# 05_Mechanical.net
KiCad netlist of a schematic drawn in Altium Designer
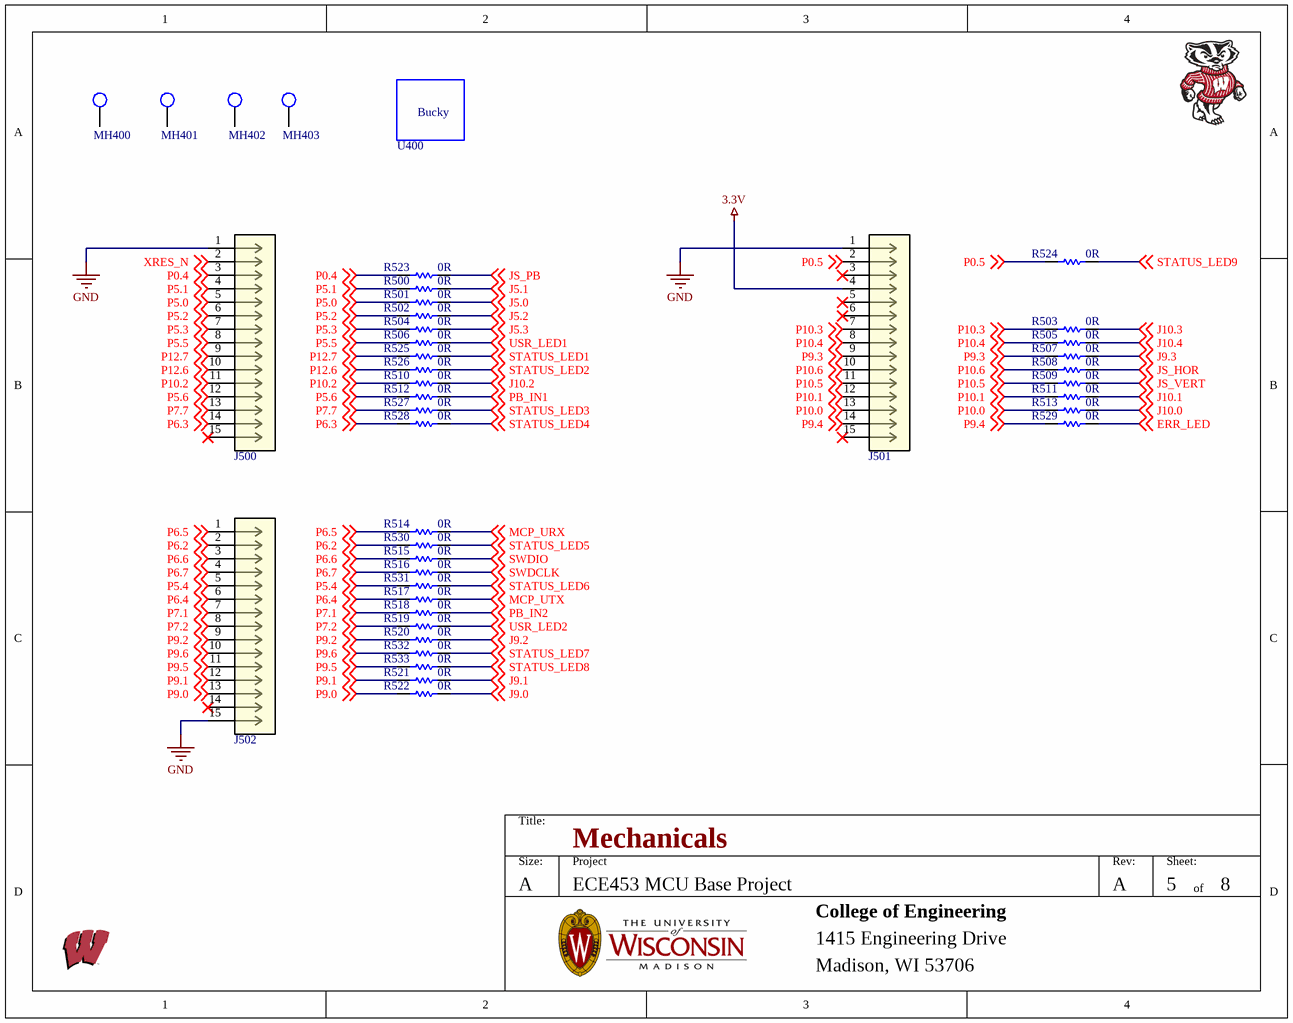
[diagram p0: 05_Mechanical.SchDoc]

(export (version "E")
  (design (tool "Eeschema 10.0.6"))
  (components
    (comp (ref "J500")
      (value "68000-115HLF")
      (footprint "CONN_15POS_2P54MM")
      (description "Conn Unshrouded Header HDR 15 POS 2.54mm Solder ST Thru-Hole")
      (fields
        (field (name "MANUFACTURER") "Adam Equipment")
        (field (name "MANUFACTURER PART NUMBER") "PH1-15-UA")
        (field (name "COPYRIGHT") "Copyright (C) 2024 Ultra Librarian. All rights reserved.")
      )
      (libsource (lib "ECE453_S24") (part "CONN_HEADER_POS_30_2.54MM"))
    )
    (comp (ref "J501")
      (value "68000-115HLF")
      (footprint "CONN_15POS_2P54MM")
      (description "Conn Unshrouded Header HDR 15 POS 2.54mm Solder ST Thru-Hole")
      (fields
        (field (name "MANUFACTURER") "Adam Equipment")
        (field (name "MANUFACTURER PART NUMBER") "PH1-15-UA")
        (field (name "COPYRIGHT") "Copyright (C) 2024 Ultra Librarian. All rights reserved.")
      )
      (libsource (lib "ECE453_S24") (part "CONN_HEADER_POS_30_2.54MM"))
    )
    (comp (ref "J502")
      (value "68000-115HLF")
      (footprint "CONN_15POS_2P54MM")
      (description "Conn Unshrouded Header HDR 15 POS 2.54mm Solder ST Thru-Hole")
      (fields
        (field (name "MANUFACTURER") "Adam Equipment")
        (field (name "MANUFACTURER PART NUMBER") "PH1-15-UA")
        (field (name "COPYRIGHT") "Copyright (C) 2024 Ultra Librarian. All rights reserved.")
      )
      (libsource (lib "ECE453_S24") (part "CONN_HEADER_POS_30_2.54MM"))
    )
    (comp (ref "MH400")
      (value "MHOLE_2_55MM")
      (footprint "MHOLE_2_55MM")
      (description "Mounting Holde")
      (fields (field (name "MANUFACTURER PART NUMBER") "UW MTHOLE"))
      (libsource (lib "ECE453_S24") (part "MHOLE_2_55MM"))
    )
    (comp (ref "MH401")
      (value "MHOLE_2_55MM")
      (footprint "MHOLE_2_55MM")
      (description "Mounting Holde")
      (fields (field (name "MANUFACTURER PART NUMBER") "UW MTHOLE"))
      (libsource (lib "ECE453_S24") (part "MHOLE_2_55MM"))
    )
    (comp (ref "MH402")
      (value "MHOLE_2_55MM")
      (footprint "MHOLE_2_55MM")
      (description "Mounting Holde")
      (fields (field (name "MANUFACTURER PART NUMBER") "UW MTHOLE"))
      (libsource (lib "ECE453_S24") (part "MHOLE_2_55MM"))
    )
    (comp (ref "MH403")
      (value "MHOLE_2_55MM")
      (footprint "MHOLE_2_55MM")
      (description "Mounting Holde")
      (fields (field (name "MANUFACTURER PART NUMBER") "UW MTHOLE"))
      (libsource (lib "ECE453_S24") (part "MHOLE_2_55MM"))
    )
    (comp (ref "R500")
      (value "0R")
      (footprint "RESC2013X70X40NL20T20")
      (description "Chip Resistor, 0 Ohm, +/- 1%, 0.125 W, -55 to 155 degC, 0805 (2012 Metric), RoHS, Tape and Reel")
      (fields (field (name "PARTNUMBER") "ERJ-6GEY0R00V") (field (name "TOLERANCE") "5%"))
      (libsource (lib "Altium Content Vault") (part "RES-2"))
    )
    (comp (ref "R501")
      (value "0R")
      (footprint "RESC2013X70X40NL20T20")
      (description "Chip Resistor, 0 Ohm, +/- 1%, 0.125 W, -55 to 155 degC, 0805 (2012 Metric), RoHS, Tape and Reel")
      (fields (field (name "PARTNUMBER") "ERJ-6GEY0R00V") (field (name "TOLERANCE") "5%"))
      (libsource (lib "Altium Content Vault") (part "RES-2"))
    )
    (comp (ref "R502")
      (value "0R")
      (footprint "RESC2013X70X40NL20T20")
      (description "Chip Resistor, 0 Ohm, +/- 1%, 0.125 W, -55 to 155 degC, 0805 (2012 Metric), RoHS, Tape and Reel")
      (fields (field (name "PARTNUMBER") "ERJ-6GEY0R00V") (field (name "TOLERANCE") "5%"))
      (libsource (lib "Altium Content Vault") (part "RES-2"))
    )
    (comp (ref "R503")
      (value "0R")
      (footprint "RESC2013X70X40NL20T20")
      (description "Chip Resistor, 0 Ohm, +/- 1%, 0.125 W, -55 to 155 degC, 0805 (2012 Metric), RoHS, Tape and Reel")
      (fields (field (name "PARTNUMBER") "ERJ-6GEY0R00V") (field (name "TOLERANCE") "5%"))
      (libsource (lib "Altium Content Vault") (part "RES-2"))
    )
    (comp (ref "R504")
      (value "0R")
      (footprint "RESC2013X70X40NL20T20")
      (description "Chip Resistor, 0 Ohm, +/- 1%, 0.125 W, -55 to 155 degC, 0805 (2012 Metric), RoHS, Tape and Reel")
      (fields (field (name "PARTNUMBER") "ERJ-6GEY0R00V") (field (name "TOLERANCE") "5%"))
      (libsource (lib "Altium Content Vault") (part "RES-2"))
    )
    (comp (ref "R505")
      (value "0R")
      (footprint "RESC2013X70X40NL20T20")
      (description "Chip Resistor, 0 Ohm, +/- 1%, 0.125 W, -55 to 155 degC, 0805 (2012 Metric), RoHS, Tape and Reel")
      (fields (field (name "PARTNUMBER") "ERJ-6GEY0R00V") (field (name "TOLERANCE") "5%"))
      (libsource (lib "Altium Content Vault") (part "RES-2"))
    )
    (comp (ref "R506")
      (value "0R")
      (footprint "RESC2013X70X40NL20T20")
      (description "Chip Resistor, 0 Ohm, +/- 1%, 0.125 W, -55 to 155 degC, 0805 (2012 Metric), RoHS, Tape and Reel")
      (fields (field (name "PARTNUMBER") "ERJ-6GEY0R00V") (field (name "TOLERANCE") "5%"))
      (libsource (lib "Altium Content Vault") (part "RES-2"))
    )
    (comp (ref "R507")
      (value "0R")
      (footprint "RESC2013X70X40NL20T20")
      (description "Chip Resistor, 0 Ohm, +/- 1%, 0.125 W, -55 to 155 degC, 0805 (2012 Metric), RoHS, Tape and Reel")
      (fields (field (name "PARTNUMBER") "ERJ-6GEY0R00V") (field (name "TOLERANCE") "5%"))
      (libsource (lib "Altium Content Vault") (part "RES-2"))
    )
    (comp (ref "R508")
      (value "0R")
      (footprint "RESC2013X70X40NL20T20")
      (description "Chip Resistor, 0 Ohm, +/- 1%, 0.125 W, -55 to 155 degC, 0805 (2012 Metric), RoHS, Tape and Reel")
      (fields (field (name "PARTNUMBER") "ERJ-6GEY0R00V") (field (name "TOLERANCE") "5%"))
      (libsource (lib "Altium Content Vault") (part "RES-2"))
    )
    (comp (ref "R509")
      (value "0R")
      (footprint "RESC2013X70X40NL20T20")
      (description "Chip Resistor, 0 Ohm, +/- 1%, 0.125 W, -55 to 155 degC, 0805 (2012 Metric), RoHS, Tape and Reel")
      (fields (field (name "PARTNUMBER") "ERJ-6GEY0R00V") (field (name "TOLERANCE") "5%"))
      (libsource (lib "Altium Content Vault") (part "RES-2"))
    )
    (comp (ref "R510")
      (value "0R")
      (footprint "RESC2013X70X40NL20T20")
      (description "Chip Resistor, 0 Ohm, +/- 1%, 0.125 W, -55 to 155 degC, 0805 (2012 Metric), RoHS, Tape and Reel")
      (fields (field (name "PARTNUMBER") "ERJ-6GEY0R00V") (field (name "TOLERANCE") "5%"))
      (libsource (lib "Altium Content Vault") (part "RES-2"))
    )
    (comp (ref "R511")
      (value "0R")
      (footprint "RESC2013X70X40NL20T20")
      (description "Chip Resistor, 0 Ohm, +/- 1%, 0.125 W, -55 to 155 degC, 0805 (2012 Metric), RoHS, Tape and Reel")
      (fields (field (name "PARTNUMBER") "ERJ-6GEY0R00V") (field (name "TOLERANCE") "5%"))
      (libsource (lib "Altium Content Vault") (part "RES-2"))
    )
    (comp (ref "R512")
      (value "0R")
      (footprint "RESC2013X70X40NL20T20")
      (description "Chip Resistor, 0 Ohm, +/- 1%, 0.125 W, -55 to 155 degC, 0805 (2012 Metric), RoHS, Tape and Reel")
      (fields (field (name "PARTNUMBER") "ERJ-6GEY0R00V") (field (name "TOLERANCE") "5%"))
      (libsource (lib "Altium Content Vault") (part "RES-2"))
    )
    (comp (ref "R513")
      (value "0R")
      (footprint "RESC2013X70X40NL20T20")
      (description "Chip Resistor, 0 Ohm, +/- 1%, 0.125 W, -55 to 155 degC, 0805 (2012 Metric), RoHS, Tape and Reel")
      (fields (field (name "PARTNUMBER") "ERJ-6GEY0R00V") (field (name "TOLERANCE") "5%"))
      (libsource (lib "Altium Content Vault") (part "RES-2"))
    )
    (comp (ref "R514")
      (value "0R")
      (footprint "RESC2013X70X40NL20T20")
      (description "Chip Resistor, 0 Ohm, +/- 1%, 0.125 W, -55 to 155 degC, 0805 (2012 Metric), RoHS, Tape and Reel")
      (fields (field (name "PARTNUMBER") "ERJ-6GEY0R00V") (field (name "TOLERANCE") "5%"))
      (libsource (lib "Altium Content Vault") (part "RES-2"))
    )
    (comp (ref "R515")
      (value "0R")
      (footprint "RESC2013X70X40NL20T20")
      (description "Chip Resistor, 0 Ohm, +/- 1%, 0.125 W, -55 to 155 degC, 0805 (2012 Metric), RoHS, Tape and Reel")
      (fields (field (name "PARTNUMBER") "ERJ-6GEY0R00V") (field (name "TOLERANCE") "5%"))
      (libsource (lib "Altium Content Vault") (part "RES-2"))
    )
    (comp (ref "R516")
      (value "0R")
      (footprint "RESC2013X70X40NL20T20")
      (description "Chip Resistor, 0 Ohm, +/- 1%, 0.125 W, -55 to 155 degC, 0805 (2012 Metric), RoHS, Tape and Reel")
      (fields (field (name "PARTNUMBER") "ERJ-6GEY0R00V") (field (name "TOLERANCE") "5%"))
      (libsource (lib "Altium Content Vault") (part "RES-2"))
    )
    (comp (ref "R517")
      (value "0R")
      (footprint "RESC2013X70X40NL20T20")
      (description "Chip Resistor, 0 Ohm, +/- 1%, 0.125 W, -55 to 155 degC, 0805 (2012 Metric), RoHS, Tape and Reel")
      (fields (field (name "PARTNUMBER") "ERJ-6GEY0R00V") (field (name "TOLERANCE") "5%"))
      (libsource (lib "Altium Content Vault") (part "RES-2"))
    )
    (comp (ref "R518")
      (value "0R")
      (footprint "RESC2013X70X40NL20T20")
      (description "Chip Resistor, 0 Ohm, +/- 1%, 0.125 W, -55 to 155 degC, 0805 (2012 Metric), RoHS, Tape and Reel")
      (fields (field (name "PARTNUMBER") "ERJ-6GEY0R00V") (field (name "TOLERANCE") "5%"))
      (libsource (lib "Altium Content Vault") (part "RES-2"))
    )
    (comp (ref "R519")
      (value "0R")
      (footprint "RESC2013X70X40NL20T20")
      (description "Chip Resistor, 0 Ohm, +/- 1%, 0.125 W, -55 to 155 degC, 0805 (2012 Metric), RoHS, Tape and Reel")
      (fields (field (name "PARTNUMBER") "ERJ-6GEY0R00V") (field (name "TOLERANCE") "5%"))
      (libsource (lib "Altium Content Vault") (part "RES-2"))
    )
    (comp (ref "R520")
      (value "0R")
      (footprint "RESC2013X70X40NL20T20")
      (description "Chip Resistor, 0 Ohm, +/- 1%, 0.125 W, -55 to 155 degC, 0805 (2012 Metric), RoHS, Tape and Reel")
      (fields (field (name "PARTNUMBER") "ERJ-6GEY0R00V") (field (name "TOLERANCE") "5%"))
      (libsource (lib "Altium Content Vault") (part "RES-2"))
    )
    (comp (ref "R521")
      (value "0R")
      (footprint "RESC2013X70X40NL20T20")
      (description "Chip Resistor, 0 Ohm, +/- 1%, 0.125 W, -55 to 155 degC, 0805 (2012 Metric), RoHS, Tape and Reel")
      (fields (field (name "PARTNUMBER") "ERJ-6GEY0R00V") (field (name "TOLERANCE") "5%"))
      (libsource (lib "Altium Content Vault") (part "RES-2"))
    )
    (comp (ref "R522")
      (value "0R")
      (footprint "RESC2013X70X40NL20T20")
      (description "Chip Resistor, 0 Ohm, +/- 1%, 0.125 W, -55 to 155 degC, 0805 (2012 Metric), RoHS, Tape and Reel")
      (fields (field (name "PARTNUMBER") "ERJ-6GEY0R00V") (field (name "TOLERANCE") "5%"))
      (libsource (lib "Altium Content Vault") (part "RES-2"))
    )
    (comp (ref "R523")
      (value "0R")
      (footprint "RESC2013X70X40NL20T20")
      (description "Chip Resistor, 0 Ohm, +/- 1%, 0.125 W, -55 to 155 degC, 0805 (2012 Metric), RoHS, Tape and Reel")
      (fields (field (name "PARTNUMBER") "ERJ-6GEY0R00V") (field (name "TOLERANCE") "5%"))
      (libsource (lib "Altium Content Vault") (part "RES-2"))
    )
    (comp (ref "R524")
      (value "0R")
      (footprint "RESC2013X70X40NL20T20")
      (description "Chip Resistor, 0 Ohm, +/- 1%, 0.125 W, -55 to 155 degC, 0805 (2012 Metric), RoHS, Tape and Reel")
      (fields (field (name "PARTNUMBER") "ERJ-6GEY0R00V") (field (name "TOLERANCE") "5%"))
      (libsource (lib "Altium Content Vault") (part "RES-2"))
    )
    (comp (ref "R525")
      (value "0R")
      (footprint "RESC2013X70X40NL20T20")
      (description "Chip Resistor, 0 Ohm, +/- 1%, 0.125 W, -55 to 155 degC, 0805 (2012 Metric), RoHS, Tape and Reel")
      (fields (field (name "PARTNUMBER") "ERJ-6GEY0R00V") (field (name "TOLERANCE") "5%"))
      (libsource (lib "Altium Content Vault") (part "RES-2"))
    )
    (comp (ref "R526")
      (value "0R")
      (footprint "RESC2013X70X40NL20T20")
      (description "Chip Resistor, 0 Ohm, +/- 1%, 0.125 W, -55 to 155 degC, 0805 (2012 Metric), RoHS, Tape and Reel")
      (fields (field (name "PARTNUMBER") "ERJ-6GEY0R00V") (field (name "TOLERANCE") "5%"))
      (libsource (lib "Altium Content Vault") (part "RES-2"))
    )
    (comp (ref "R527")
      (value "0R")
      (footprint "RESC2013X70X40NL20T20")
      (description "Chip Resistor, 0 Ohm, +/- 1%, 0.125 W, -55 to 155 degC, 0805 (2012 Metric), RoHS, Tape and Reel")
      (fields (field (name "PARTNUMBER") "ERJ-6GEY0R00V") (field (name "TOLERANCE") "5%"))
      (libsource (lib "Altium Content Vault") (part "RES-2"))
    )
    (comp (ref "R528")
      (value "0R")
      (footprint "RESC2013X70X40NL20T20")
      (description "Chip Resistor, 0 Ohm, +/- 1%, 0.125 W, -55 to 155 degC, 0805 (2012 Metric), RoHS, Tape and Reel")
      (fields (field (name "PARTNUMBER") "ERJ-6GEY0R00V") (field (name "TOLERANCE") "5%"))
      (libsource (lib "Altium Content Vault") (part "RES-2"))
    )
    (comp (ref "R529")
      (value "0R")
      (footprint "RESC2013X70X40NL20T20")
      (description "Chip Resistor, 0 Ohm, +/- 1%, 0.125 W, -55 to 155 degC, 0805 (2012 Metric), RoHS, Tape and Reel")
      (fields (field (name "PARTNUMBER") "ERJ-6GEY0R00V") (field (name "TOLERANCE") "5%"))
      (libsource (lib "Altium Content Vault") (part "RES-2"))
    )
    (comp (ref "R530")
      (value "0R")
      (footprint "RESC2013X70X40NL20T20")
      (description "Chip Resistor, 0 Ohm, +/- 1%, 0.125 W, -55 to 155 degC, 0805 (2012 Metric), RoHS, Tape and Reel")
      (fields (field (name "PARTNUMBER") "ERJ-6GEY0R00V") (field (name "TOLERANCE") "5%"))
      (libsource (lib "Altium Content Vault") (part "RES-2"))
    )
    (comp (ref "R531")
      (value "0R")
      (footprint "RESC2013X70X40NL20T20")
      (description "Chip Resistor, 0 Ohm, +/- 1%, 0.125 W, -55 to 155 degC, 0805 (2012 Metric), RoHS, Tape and Reel")
      (fields (field (name "PARTNUMBER") "ERJ-6GEY0R00V") (field (name "TOLERANCE") "5%"))
      (libsource (lib "Altium Content Vault") (part "RES-2"))
    )
    (comp (ref "R532")
      (value "0R")
      (footprint "RESC2013X70X40NL20T20")
      (description "Chip Resistor, 0 Ohm, +/- 1%, 0.125 W, -55 to 155 degC, 0805 (2012 Metric), RoHS, Tape and Reel")
      (fields (field (name "PARTNUMBER") "ERJ-6GEY0R00V") (field (name "TOLERANCE") "5%"))
      (libsource (lib "Altium Content Vault") (part "RES-2"))
    )
    (comp (ref "R533")
      (value "0R")
      (footprint "RESC2013X70X40NL20T20")
      (description "Chip Resistor, 0 Ohm, +/- 1%, 0.125 W, -55 to 155 degC, 0805 (2012 Metric), RoHS, Tape and Reel")
      (fields (field (name "PARTNUMBER") "ERJ-6GEY0R00V") (field (name "TOLERANCE") "5%"))
      (libsource (lib "Altium Content Vault") (part "RES-2"))
    )
    (comp (ref "U400")
      (value "Bucky")
      (footprint "WalkingBucky")
      (description "Bucky Badger Image")
      (fields (field (name "MANUFACTURER PART NUMBER") "UW Bucky"))
      (libsource (lib "ECE453") (part "Bucky"))
    )
  )
  (nets
    (net (code "1") (name "3.3V") (class "Default")
      (node (ref "J501") (pin "4") (pinfunction "4_4") (pintype "passive"))
    )
    (net (code "2") (name "ERR_LED") (class "Default")
      (node (ref "R529") (pin "2") (pinfunction "2_2") (pintype "passive"))
    )
    (net (code "3") (name "GND") (class "Default")
      (node (ref "J500") (pin "1") (pinfunction "1_1") (pintype "passive"))
      (node (ref "J501") (pin "1") (pinfunction "1_1") (pintype "passive"))
      (node (ref "J502") (pin "15") (pinfunction "15_15") (pintype "passive"))
    )
    (net (code "4") (name "J5.0") (class "Default")
      (node (ref "R501") (pin "2") (pinfunction "2_2") (pintype "passive"))
    )
    (net (code "5") (name "J5.1") (class "Default")
      (node (ref "R500") (pin "2") (pinfunction "2_2") (pintype "passive"))
    )
    (net (code "6") (name "J5.2") (class "Default")
      (node (ref "R502") (pin "2") (pinfunction "2_2") (pintype "passive"))
    )
    (net (code "7") (name "J5.3") (class "Default")
      (node (ref "R504") (pin "2") (pinfunction "2_2") (pintype "passive"))
    )
    (net (code "8") (name "J9.0") (class "Default")
      (node (ref "R522") (pin "2") (pinfunction "2_2") (pintype "passive"))
    )
    (net (code "9") (name "J9.1") (class "Default")
      (node (ref "R521") (pin "2") (pinfunction "2_2") (pintype "passive"))
    )
    (net (code "10") (name "J9.2") (class "Default")
      (node (ref "R520") (pin "2") (pinfunction "2_2") (pintype "passive"))
    )
    (net (code "11") (name "J9.3") (class "Default")
      (node (ref "R507") (pin "2") (pinfunction "2_2") (pintype "passive"))
    )
    (net (code "12") (name "J10.0") (class "Default")
      (node (ref "R513") (pin "2") (pinfunction "2_2") (pintype "passive"))
    )
    (net (code "13") (name "J10.1") (class "Default")
      (node (ref "R511") (pin "2") (pinfunction "2_2") (pintype "passive"))
    )
    (net (code "14") (name "J10.2") (class "Default")
      (node (ref "R510") (pin "2") (pinfunction "2_2") (pintype "passive"))
    )
    (net (code "15") (name "J10.3") (class "Default")
      (node (ref "R503") (pin "2") (pinfunction "2_2") (pintype "passive"))
    )
    (net (code "16") (name "J10.4") (class "Default")
      (node (ref "R505") (pin "2") (pinfunction "2_2") (pintype "passive"))
    )
    (net (code "17") (name "JS_HOR") (class "Default")
      (node (ref "R508") (pin "2") (pinfunction "2_2") (pintype "passive"))
    )
    (net (code "18") (name "JS_PB") (class "Default")
      (node (ref "R523") (pin "2") (pinfunction "2_2") (pintype "passive"))
    )
    (net (code "19") (name "JS_VERT") (class "Default")
      (node (ref "R509") (pin "2") (pinfunction "2_2") (pintype "passive"))
    )
    (net (code "20") (name "MCP_URX") (class "Default")
      (node (ref "R514") (pin "2") (pinfunction "2_2") (pintype "passive"))
    )
    (net (code "21") (name "MCP_UTX") (class "Default")
      (node (ref "R517") (pin "2") (pinfunction "2_2") (pintype "passive"))
    )
    (net (code "22") (name "P0.4") (class "Default")
      (node (ref "J500") (pin "3") (pinfunction "3_3") (pintype "passive"))
      (node (ref "R523") (pin "1") (pinfunction "1_1") (pintype "passive"))
    )
    (net (code "23") (name "P0.5") (class "Default")
      (node (ref "J501") (pin "2") (pinfunction "2_2") (pintype "passive"))
      (node (ref "R524") (pin "1") (pinfunction "1_1") (pintype "passive"))
    )
    (net (code "24") (name "P5.0") (class "Default")
      (node (ref "J500") (pin "5") (pinfunction "5_5") (pintype "passive"))
      (node (ref "R501") (pin "1") (pinfunction "1_1") (pintype "passive"))
    )
    (net (code "25") (name "P5.1") (class "Default")
      (node (ref "J500") (pin "4") (pinfunction "4_4") (pintype "passive"))
      (node (ref "R500") (pin "1") (pinfunction "1_1") (pintype "passive"))
    )
    (net (code "26") (name "P5.2") (class "Default")
      (node (ref "J500") (pin "6") (pinfunction "6_6") (pintype "passive"))
      (node (ref "R502") (pin "1") (pinfunction "1_1") (pintype "passive"))
    )
    (net (code "27") (name "P5.3") (class "Default")
      (node (ref "J500") (pin "7") (pinfunction "7_7") (pintype "passive"))
      (node (ref "R504") (pin "1") (pinfunction "1_1") (pintype "passive"))
    )
    (net (code "28") (name "P5.4") (class "Default")
      (node (ref "J502") (pin "5") (pinfunction "5_5") (pintype "passive"))
      (node (ref "R531") (pin "1") (pinfunction "1_1") (pintype "passive"))
    )
    (net (code "29") (name "P5.5") (class "Default")
      (node (ref "J500") (pin "8") (pinfunction "8_8") (pintype "passive"))
      (node (ref "R506") (pin "1") (pinfunction "1_1") (pintype "passive"))
    )
    (net (code "30") (name "P5.6") (class "Default")
      (node (ref "J500") (pin "12") (pinfunction "12_12") (pintype "passive"))
      (node (ref "R512") (pin "1") (pinfunction "1_1") (pintype "passive"))
    )
    (net (code "31") (name "P6.2") (class "Default")
      (node (ref "J502") (pin "2") (pinfunction "2_2") (pintype "passive"))
      (node (ref "R530") (pin "1") (pinfunction "1_1") (pintype "passive"))
    )
    (net (code "32") (name "P6.3") (class "Default")
      (node (ref "J500") (pin "14") (pinfunction "14_14") (pintype "passive"))
      (node (ref "R528") (pin "1") (pinfunction "1_1") (pintype "passive"))
    )
    (net (code "33") (name "P6.4") (class "Default")
      (node (ref "J502") (pin "6") (pinfunction "6_6") (pintype "passive"))
      (node (ref "R517") (pin "1") (pinfunction "1_1") (pintype "passive"))
    )
    (net (code "34") (name "P6.5") (class "Default")
      (node (ref "J502") (pin "1") (pinfunction "1_1") (pintype "passive"))
      (node (ref "R514") (pin "1") (pinfunction "1_1") (pintype "passive"))
    )
    (net (code "35") (name "P6.6") (class "Default")
      (node (ref "J502") (pin "3") (pinfunction "3_3") (pintype "passive"))
      (node (ref "R515") (pin "1") (pinfunction "1_1") (pintype "passive"))
    )
    (net (code "36") (name "P6.7") (class "Default")
      (node (ref "J502") (pin "4") (pinfunction "4_4") (pintype "passive"))
      (node (ref "R516") (pin "1") (pinfunction "1_1") (pintype "passive"))
    )
    (net (code "37") (name "P7.1") (class "Default")
      (node (ref "J502") (pin "7") (pinfunction "7_7") (pintype "passive"))
      (node (ref "R518") (pin "1") (pinfunction "1_1") (pintype "passive"))
    )
    (net (code "38") (name "P7.2") (class "Default")
      (node (ref "J502") (pin "8") (pinfunction "8_8") (pintype "passive"))
      (node (ref "R519") (pin "1") (pinfunction "1_1") (pintype "passive"))
    )
    (net (code "39") (name "P7.7") (class "Default")
      (node (ref "J500") (pin "13") (pinfunction "13_13") (pintype "passive"))
      (node (ref "R527") (pin "1") (pinfunction "1_1") (pintype "passive"))
    )
    (net (code "40") (name "P9.0") (class "Default")
      (node (ref "J502") (pin "13") (pinfunction "13_13") (pintype "passive"))
      (node (ref "R522") (pin "1") (pinfunction "1_1") (pintype "passive"))
    )
    (net (code "41") (name "P9.1") (class "Default")
      (node (ref "J502") (pin "12") (pinfunction "12_12") (pintype "passive"))
      (node (ref "R521") (pin "1") (pinfunction "1_1") (pintype "passive"))
    )
    (net (code "42") (name "P9.2") (class "Default")
      (node (ref "J502") (pin "9") (pinfunction "9_9") (pintype "passive"))
      (node (ref "R520") (pin "1") (pinfunction "1_1") (pintype "passive"))
    )
    (net (code "43") (name "P9.3") (class "Default")
      (node (ref "J501") (pin "9") (pinfunction "9_9") (pintype "passive"))
      (node (ref "R507") (pin "1") (pinfunction "1_1") (pintype "passive"))
    )
    (net (code "44") (name "P9.4") (class "Default")
      (node (ref "J501") (pin "14") (pinfunction "14_14") (pintype "passive"))
      (node (ref "R529") (pin "1") (pinfunction "1_1") (pintype "passive"))
    )
    (net (code "45") (name "P9.5") (class "Default")
      (node (ref "J502") (pin "11") (pinfunction "11_11") (pintype "passive"))
      (node (ref "R533") (pin "1") (pinfunction "1_1") (pintype "passive"))
    )
    (net (code "46") (name "P9.6") (class "Default")
      (node (ref "J502") (pin "10") (pinfunction "10_10") (pintype "passive"))
      (node (ref "R532") (pin "1") (pinfunction "1_1") (pintype "passive"))
    )
    (net (code "47") (name "P10.0") (class "Default")
      (node (ref "J501") (pin "13") (pinfunction "13_13") (pintype "passive"))
      (node (ref "R513") (pin "1") (pinfunction "1_1") (pintype "passive"))
    )
    (net (code "48") (name "P10.1") (class "Default")
      (node (ref "J501") (pin "12") (pinfunction "12_12") (pintype "passive"))
      (node (ref "R511") (pin "1") (pinfunction "1_1") (pintype "passive"))
    )
    (net (code "49") (name "P10.2") (class "Default")
      (node (ref "J500") (pin "11") (pinfunction "11_11") (pintype "passive"))
      (node (ref "R510") (pin "1") (pinfunction "1_1") (pintype "passive"))
    )
    (net (code "50") (name "P10.3") (class "Default")
      (node (ref "J501") (pin "7") (pinfunction "7_7") (pintype "passive"))
      (node (ref "R503") (pin "1") (pinfunction "1_1") (pintype "passive"))
    )
    (net (code "51") (name "P10.4") (class "Default")
      (node (ref "J501") (pin "8") (pinfunction "8_8") (pintype "passive"))
      (node (ref "R505") (pin "1") (pinfunction "1_1") (pintype "passive"))
    )
    (net (code "52") (name "P10.5") (class "Default")
      (node (ref "J501") (pin "11") (pinfunction "11_11") (pintype "passive"))
      (node (ref "R509") (pin "1") (pinfunction "1_1") (pintype "passive"))
    )
    (net (code "53") (name "P10.6") (class "Default")
      (node (ref "J501") (pin "10") (pinfunction "10_10") (pintype "passive"))
      (node (ref "R508") (pin "1") (pinfunction "1_1") (pintype "passive"))
    )
    (net (code "54") (name "P12.6") (class "Default")
      (node (ref "J500") (pin "10") (pinfunction "10_10") (pintype "passive"))
      (node (ref "R526") (pin "1") (pinfunction "1_1") (pintype "passive"))
    )
    (net (code "55") (name "P12.7") (class "Default")
      (node (ref "J500") (pin "9") (pinfunction "9_9") (pintype "passive"))
      (node (ref "R525") (pin "1") (pinfunction "1_1") (pintype "passive"))
    )
    (net (code "56") (name "PB_IN1") (class "Default")
      (node (ref "R512") (pin "2") (pinfunction "2_2") (pintype "passive"))
    )
    (net (code "57") (name "PB_IN2") (class "Default")
      (node (ref "R518") (pin "2") (pinfunction "2_2") (pintype "passive"))
    )
    (net (code "58") (name "STATUS_LED1") (class "Default")
      (node (ref "R525") (pin "2") (pinfunction "2_2") (pintype "passive"))
    )
    (net (code "59") (name "STATUS_LED2") (class "Default")
      (node (ref "R526") (pin "2") (pinfunction "2_2") (pintype "passive"))
    )
    (net (code "60") (name "STATUS_LED3") (class "Default")
      (node (ref "R527") (pin "2") (pinfunction "2_2") (pintype "passive"))
    )
    (net (code "61") (name "STATUS_LED4") (class "Default")
      (node (ref "R528") (pin "2") (pinfunction "2_2") (pintype "passive"))
    )
    (net (code "62") (name "STATUS_LED5") (class "Default")
      (node (ref "R530") (pin "2") (pinfunction "2_2") (pintype "passive"))
    )
    (net (code "63") (name "STATUS_LED6") (class "Default")
      (node (ref "R531") (pin "2") (pinfunction "2_2") (pintype "passive"))
    )
    (net (code "64") (name "STATUS_LED7") (class "Default")
      (node (ref "R532") (pin "2") (pinfunction "2_2") (pintype "passive"))
    )
    (net (code "65") (name "STATUS_LED8") (class "Default")
      (node (ref "R533") (pin "2") (pinfunction "2_2") (pintype "passive"))
    )
    (net (code "66") (name "STATUS_LED9") (class "Default")
      (node (ref "R524") (pin "2") (pinfunction "2_2") (pintype "passive"))
    )
    (net (code "67") (name "SWDCLK") (class "Default")
      (node (ref "R516") (pin "2") (pinfunction "2_2") (pintype "passive"))
    )
    (net (code "68") (name "SWDIO") (class "Default")
      (node (ref "R515") (pin "2") (pinfunction "2_2") (pintype "passive"))
    )
    (net (code "69") (name "USR_LED1") (class "Default")
      (node (ref "R506") (pin "2") (pinfunction "2_2") (pintype "passive"))
    )
    (net (code "70") (name "USR_LED2") (class "Default")
      (node (ref "R519") (pin "2") (pinfunction "2_2") (pintype "passive"))
    )
    (net (code "71") (name "XRES_N") (class "Default")
      (node (ref "J500") (pin "2") (pinfunction "2_2") (pintype "passive"))
    )
    (net (code "72") (name "unconnected-(J500-Pad15)") (class "Default")
      (node (ref "J500") (pin "15") (pinfunction "15_15") (pintype "passive+no_connect"))
    )
    (net (code "73") (name "unconnected-(J501-Pad3)") (class "Default")
      (node (ref "J501") (pin "3") (pinfunction "3_3") (pintype "passive+no_connect"))
    )
    (net (code "74") (name "unconnected-(J501-Pad5)") (class "Default")
      (node (ref "J501") (pin "5") (pinfunction "5_5") (pintype "passive+no_connect"))
    )
    (net (code "75") (name "unconnected-(J501-Pad6)") (class "Default")
      (node (ref "J501") (pin "6") (pinfunction "6_6") (pintype "passive+no_connect"))
    )
    (net (code "76") (name "unconnected-(J501-Pad15)") (class "Default")
      (node (ref "J501") (pin "15") (pinfunction "15_15") (pintype "passive+no_connect"))
    )
    (net (code "77") (name "unconnected-(J502-Pad14)") (class "Default")
      (node (ref "J502") (pin "14") (pinfunction "14_14") (pintype "passive+no_connect"))
    )
    (net (code "78") (name "unconnected-(MH400-Pad1)") (class "Default")
      (node (ref "MH400") (pin "1") (pintype "passive"))
    )
    (net (code "79") (name "unconnected-(MH401-Pad1)") (class "Default")
      (node (ref "MH401") (pin "1") (pintype "passive"))
    )
    (net (code "80") (name "unconnected-(MH402-Pad1)") (class "Default")
      (node (ref "MH402") (pin "1") (pintype "passive"))
    )
    (net (code "81") (name "unconnected-(MH403-Pad1)") (class "Default")
      (node (ref "MH403") (pin "1") (pintype "passive"))
    )
  )
)
